# connectors.net
KiCad netlist of a schematic drawn in EAGLE
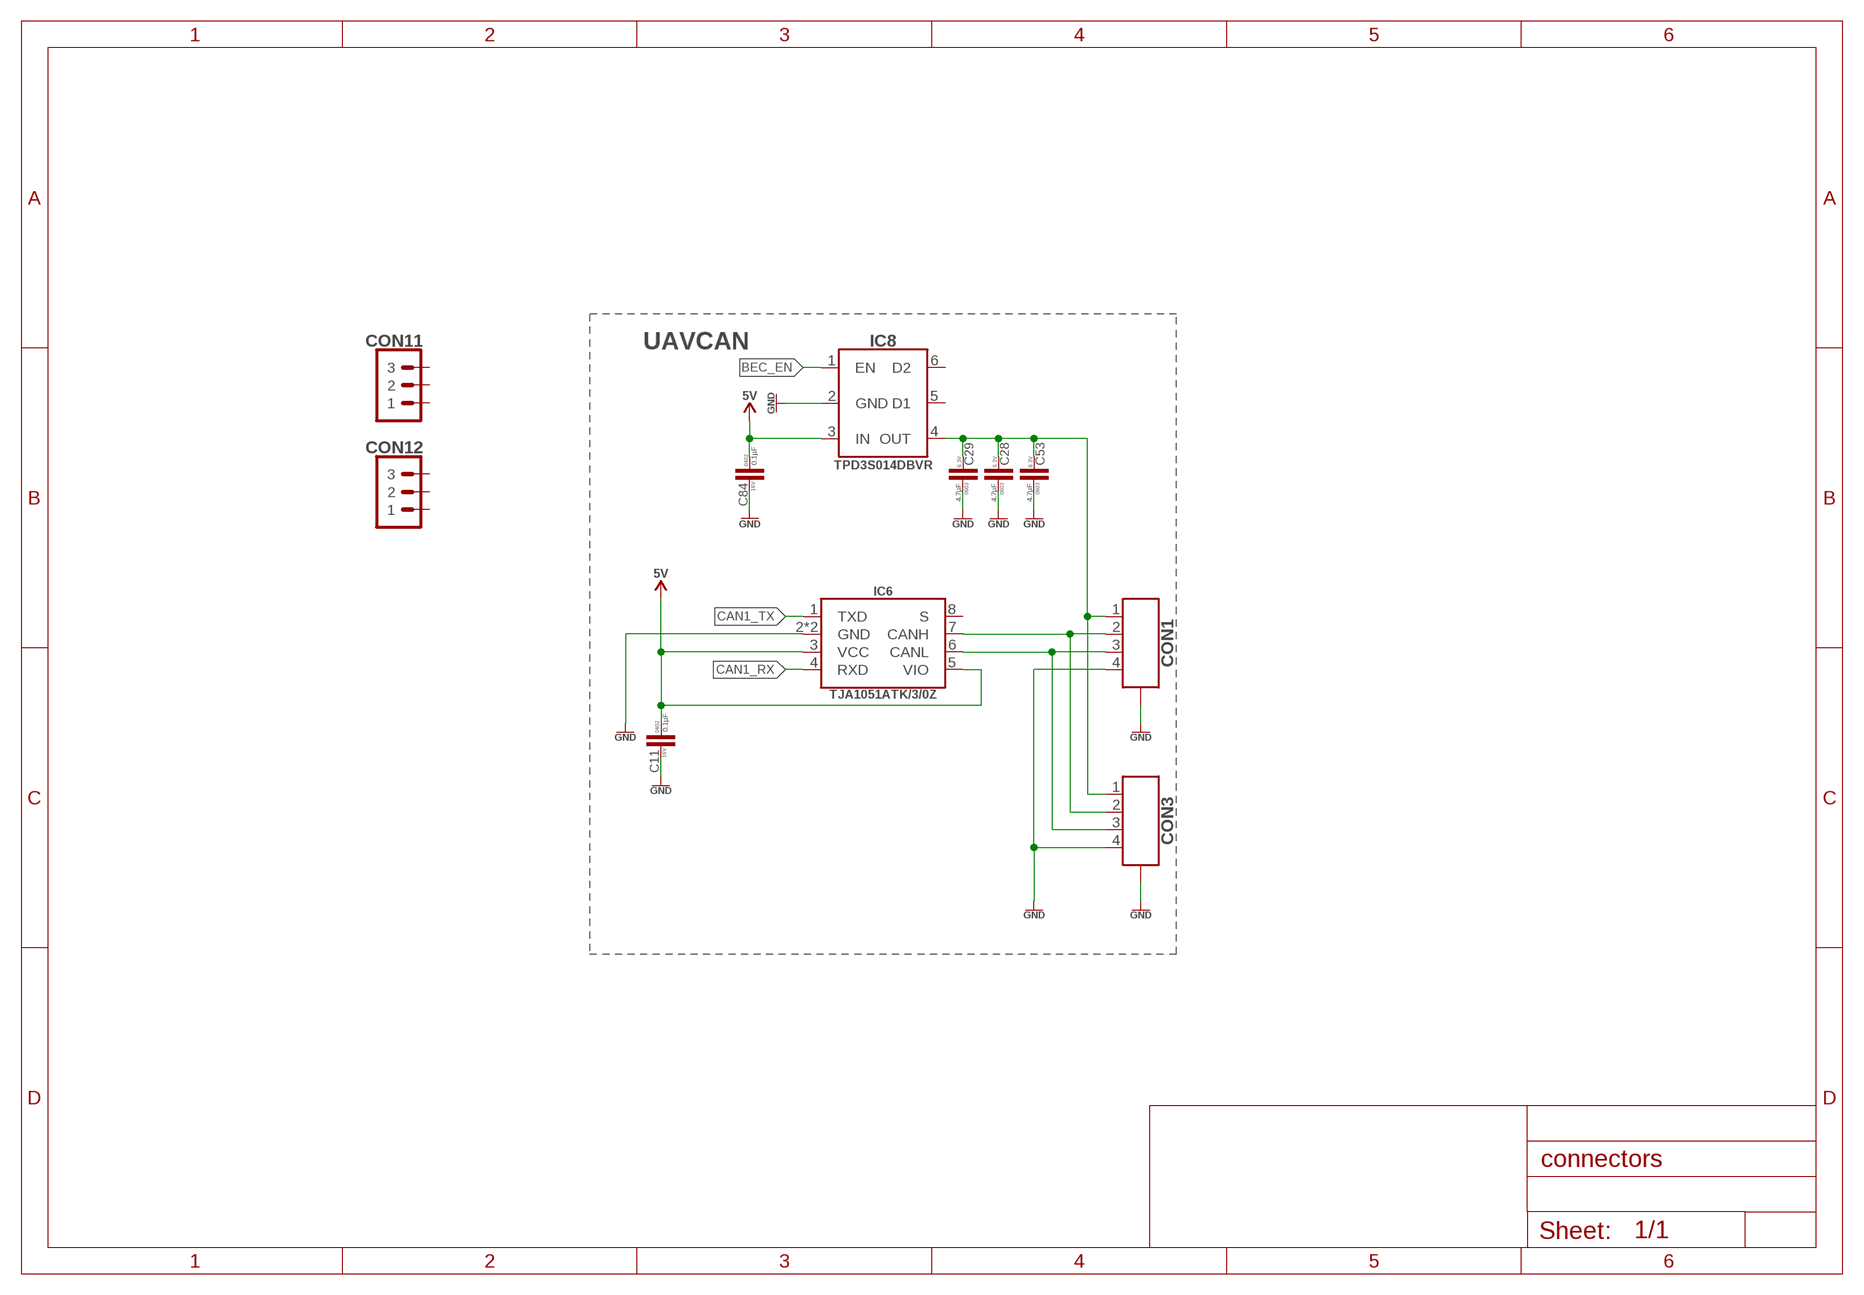
[diagram p0: schematic, sheet 1]

(export (version "E")
  (design (tool "Eeschema 10.0.6"))
  (components
    (comp (ref "C11")
      (value "0.1µF")
      (footprint "eagle-import:C0402")
      (fields
        (field (name "PACKAGE") "0402")
        (field (name "AEC-Q") "---")
        (field (name "DIGIKEY#") "490-3261-1-ND")
        (field (name "MANF") "Murata Electronics")
        (field (name "MANF#") "GRM155R71C104KA88D")
        (field (name "OPERATING_TEMP") "-55°C ~ 125°C")
        (field (name "VOLTAGE") "16V")
      )
      (libsource (lib "eagle-import") (part "C-0402"))
    )
    (comp (ref "C28")
      (value "4.7µF")
      (footprint "eagle-import:C0603")
      (fields
        (field (name "PACKAGE") "0603")
        (field (name "AEC-Q") "---")
        (field (name "DIGIKEY#") "1276-2087-1-ND")
        (field (name "MANF") "Samsung Electro-Mechanics")
        (field (name "MANF#") "CL10B475KQ8NQNC")
        (field (name "OPERATING_TEMP") "-55°C ~ 125°C")
        (field (name "VOLTAGE") "6.3V")
      )
      (libsource (lib "eagle-import") (part "C-0603"))
    )
    (comp (ref "C29")
      (value "4.7µF")
      (footprint "eagle-import:C0603")
      (fields
        (field (name "PACKAGE") "0603")
        (field (name "AEC-Q") "---")
        (field (name "DIGIKEY#") "1276-2087-1-ND")
        (field (name "MANF") "Samsung Electro-Mechanics")
        (field (name "MANF#") "CL10B475KQ8NQNC")
        (field (name "OPERATING_TEMP") "-55°C ~ 125°C")
        (field (name "VOLTAGE") "6.3V")
      )
      (libsource (lib "eagle-import") (part "C-0603"))
    )
    (comp (ref "C53")
      (value "4.7µF")
      (footprint "eagle-import:C0603")
      (fields
        (field (name "PACKAGE") "0603")
        (field (name "AEC-Q") "---")
        (field (name "DIGIKEY#") "1276-2087-1-ND")
        (field (name "MANF") "Samsung Electro-Mechanics")
        (field (name "MANF#") "CL10B475KQ8NQNC")
        (field (name "OPERATING_TEMP") "-55°C ~ 125°C")
        (field (name "VOLTAGE") "6.3V")
      )
      (libsource (lib "eagle-import") (part "C-0603"))
    )
    (comp (ref "C84")
      (value "0.1µF")
      (footprint "eagle-import:C0402")
      (fields
        (field (name "PACKAGE") "0402")
        (field (name "AEC-Q") "---")
        (field (name "DIGIKEY#") "490-3261-1-ND")
        (field (name "MANF") "Murata Electronics")
        (field (name "MANF#") "GRM155R71C104KA88D")
        (field (name "OPERATING_TEMP") "-55°C ~ 125°C")
        (field (name "VOLTAGE") "16V")
      )
      (libsource (lib "eagle-import") (part "C-0402"))
    )
    (comp (ref "CON1")
      (value "CON-4P-TABS-JST_GH-RA")
      (footprint "eagle-import:JST_GH-4P-RA")
      (fields (field (name "MANF") "JST Sales America Inc"))
      (libsource (lib "eagle-import") (part "CON-4P-TABS-RA-JST_GH"))
    )
    (comp (ref "CON3")
      (value "CON-4P-TABS-JST_GH-RA")
      (footprint "eagle-import:JST_GH-4P-RA")
      (fields (field (name "MANF") "JST Sales America Inc"))
      (libsource (lib "eagle-import") (part "CON-4P-TABS-RA-JST_GH"))
    )
    (comp (ref "CON11")
      (value "PINHEAD_1X03-2")
      (footprint "eagle-import:1X03-PTH-2")
      (libsource (lib "eagle-import") (part "PINHEAD_1X03-2"))
    )
    (comp (ref "CON12")
      (value "PINHEAD_1X03-2")
      (footprint "eagle-import:1X03-PTH-2")
      (libsource (lib "eagle-import") (part "PINHEAD_1X03-2"))
    )
    (comp (ref "IC6")
      (value "TJA1051-HVSON8")
      (footprint "eagle-import:SOT782-1")
      (fields (field (name "MANF#") "TJA1051ATK/3/0Z") (field (name "MANF") "NXP USA Inc."))
      (libsource (lib "eagle-import") (part "TJA1051-HVSON8"))
    )
    (comp (ref "IC8")
      (value "TPD3S014DBVR-SOT23-6")
      (footprint "eagle-import:SOT26")
      (fields (field (name "MANF#") "TPD3S014DBVR") (field (name "MANF") "Texas Instruments"))
      (libsource (lib "eagle-import") (part "TPD3S014DBVR-SOT23-6"))
    )
  )
  (nets
    (net (code "1") (name "5V") (class "Default")
      (node (ref "C11") (pin "1") (pinfunction "1_1") (pintype "passive"))
      (node (ref "C84") (pin "1") (pinfunction "1_1") (pintype "passive"))
      (node (ref "IC6") (pin "3") (pinfunction "VCC_3") (pintype "bidirectional"))
      (node (ref "IC6") (pin "5") (pinfunction "VIO_5") (pintype "bidirectional"))
      (node (ref "IC8") (pin "3") (pinfunction "IN_3") (pintype "bidirectional"))
    )
    (net (code "2") (name "BEC_EN") (class "Default")
      (node (ref "IC8") (pin "1") (pinfunction "EN_1") (pintype "bidirectional"))
    )
    (net (code "3") (name "CAN1_RX") (class "Default")
      (node (ref "IC6") (pin "4") (pinfunction "RXD_4") (pintype "bidirectional"))
    )
    (net (code "4") (name "CAN1_TX") (class "Default")
      (node (ref "IC6") (pin "1") (pinfunction "TXD_1") (pintype "bidirectional"))
    )
    (net (code "5") (name "GND") (class "Default")
      (node (ref "C11") (pin "2") (pinfunction "2_2") (pintype "passive"))
      (node (ref "C28") (pin "1") (pinfunction "1_1") (pintype "passive"))
      (node (ref "C29") (pin "1") (pinfunction "1_1") (pintype "passive"))
      (node (ref "C53") (pin "1") (pinfunction "1_1") (pintype "passive"))
      (node (ref "C84") (pin "2") (pinfunction "2_2") (pintype "passive"))
      (node (ref "CON1") (pin "4") (pinfunction "4_4") (pintype "bidirectional"))
      (node (ref "CON1") (pin "M$0") (pinfunction "GND_M$0") (pintype "bidirectional"))
      (node (ref "CON1") (pin "M$1") (pinfunction "GND_M$1") (pintype "bidirectional"))
      (node (ref "CON3") (pin "4") (pinfunction "4_4") (pintype "bidirectional"))
      (node (ref "CON3") (pin "M$0") (pinfunction "GND_M$0") (pintype "bidirectional"))
      (node (ref "CON3") (pin "M$1") (pinfunction "GND_M$1") (pintype "bidirectional"))
      (node (ref "IC6") (pin "2") (pinfunction "GND_2") (pintype "bidirectional"))
      (node (ref "IC6") (pin "PAD") (pinfunction "GND_PAD") (pintype "bidirectional"))
      (node (ref "IC8") (pin "2") (pinfunction "GND_2") (pintype "bidirectional"))
    )
    (net (code "6") (name "Net-(IC6-CANH)") (class "Default")
      (node (ref "CON1") (pin "2") (pinfunction "2_2") (pintype "bidirectional"))
      (node (ref "CON3") (pin "2") (pinfunction "2_2") (pintype "bidirectional"))
      (node (ref "IC6") (pin "7") (pinfunction "CANH_7") (pintype "bidirectional"))
    )
    (net (code "7") (name "Net-(IC6-CANL)") (class "Default")
      (node (ref "CON1") (pin "3") (pinfunction "3_3") (pintype "bidirectional"))
      (node (ref "CON3") (pin "3") (pinfunction "3_3") (pintype "bidirectional"))
      (node (ref "IC6") (pin "6") (pinfunction "CANL_6") (pintype "bidirectional"))
    )
    (net (code "8") (name "Net-(IC8-OUT)") (class "Default")
      (node (ref "C28") (pin "2") (pinfunction "2_2") (pintype "passive"))
      (node (ref "C29") (pin "2") (pinfunction "2_2") (pintype "passive"))
      (node (ref "C53") (pin "2") (pinfunction "2_2") (pintype "passive"))
      (node (ref "CON1") (pin "1") (pinfunction "1_1") (pintype "bidirectional"))
      (node (ref "CON3") (pin "1") (pinfunction "1_1") (pintype "bidirectional"))
      (node (ref "IC8") (pin "4") (pinfunction "OUT_4") (pintype "bidirectional"))
    )
    (net (code "9") (name "unconnected-(CON11-Pad1)") (class "Default")
      (node (ref "CON11") (pin "1") (pinfunction "1_1") (pintype "passive"))
    )
    (net (code "10") (name "unconnected-(CON11-Pad2)") (class "Default")
      (node (ref "CON11") (pin "2") (pinfunction "2_2") (pintype "passive"))
    )
    (net (code "11") (name "unconnected-(CON11-Pad3)") (class "Default")
      (node (ref "CON11") (pin "3") (pinfunction "3_3") (pintype "passive"))
    )
    (net (code "12") (name "unconnected-(CON12-Pad1)") (class "Default")
      (node (ref "CON12") (pin "1") (pinfunction "1_1") (pintype "passive"))
    )
    (net (code "13") (name "unconnected-(CON12-Pad2)") (class "Default")
      (node (ref "CON12") (pin "2") (pinfunction "2_2") (pintype "passive"))
    )
    (net (code "14") (name "unconnected-(CON12-Pad3)") (class "Default")
      (node (ref "CON12") (pin "3") (pinfunction "3_3") (pintype "passive"))
    )
    (net (code "15") (name "unconnected-(IC6-S-Pad8)") (class "Default")
      (node (ref "IC6") (pin "8") (pinfunction "S_8") (pintype "bidirectional"))
    )
    (net (code "16") (name "unconnected-(IC8-D1-Pad5)") (class "Default")
      (node (ref "IC8") (pin "5") (pinfunction "D1_5") (pintype "bidirectional"))
    )
    (net (code "17") (name "unconnected-(IC8-D2-Pad6)") (class "Default")
      (node (ref "IC8") (pin "6") (pinfunction "D2_6") (pintype "bidirectional"))
    )
  )
)
